# AmbientLight-2.net
KiCad netlist of a schematic drawn in EAGLE
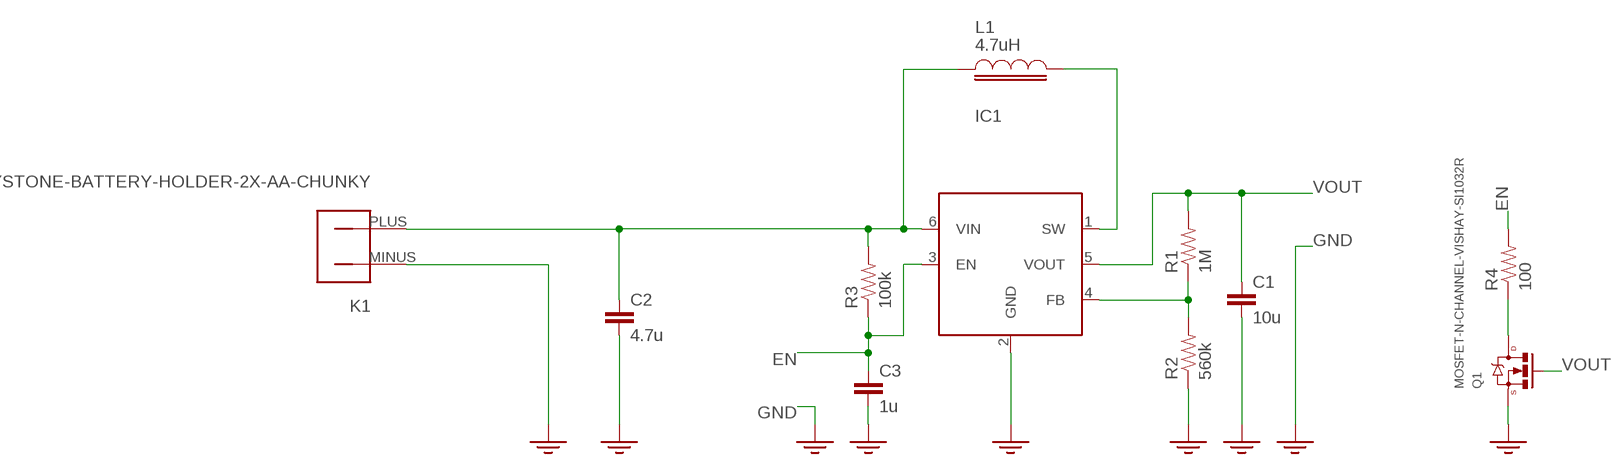
[diagram p0: schematic, sheet 1]

(export (version "E")
  (design (tool "Eeschema 10.0.6"))
  (components
    (comp (ref "C1")
      (value "10u")
      (footprint "eagle-import:0805-WIDE")
      (libsource (lib "eagle-import") (part "CAP-0805-WIDE"))
    )
    (comp (ref "C2")
      (value "4.7u")
      (footprint "eagle-import:0603-MIN")
      (libsource (lib "eagle-import") (part "CAP-0603-MIN"))
    )
    (comp (ref "C3")
      (value "1u")
      (footprint "eagle-import:0603-MIN")
      (libsource (lib "eagle-import") (part "CAP-0603-MIN"))
    )
    (comp (ref "IC1")
      (value "SWITCHING-REGULATOR-VARIABLE-BOOST-MCP1640")
      (footprint "eagle-import:SOT23-6")
      (libsource (lib "eagle-import") (part "SWITCHING-REGULATOR-VARIABLE-BOOST-MCP1640"))
    )
    (comp (ref "K1")
      (value "KEYSTONE-BATTERY-HOLDER-2X-AA-CHUNKY")
      (footprint "eagle-import:KEYSTONE-BATTERY-HOLDER-2X-AA-CHUNKY")
      (libsource (lib "eagle-import") (part "KEYSTONE-BATTERY-HOLDER-2X-AA-CHUNKY"))
    )
    (comp (ref "L1")
      (value "4.7uH")
      (footprint "eagle-import:1210-INDUCTOR-MIN")
      (libsource (lib "eagle-import") (part "INDUCTOR-1210-MIN"))
    )
    (comp (ref "Q1")
      (value "MOSFET-N-CHANNEL-VISHAY-SI1032R")
      (footprint "eagle-import:SC-75A")
      (libsource (lib "eagle-import") (part "MOSFET-N-CHANNEL-VISHAY-SI1032R"))
    )
    (comp (ref "R1")
      (value "1M")
      (footprint "eagle-import:0603-MIN")
      (libsource (lib "eagle-import") (part "RESISTOR-0603-MIN"))
    )
    (comp (ref "R2")
      (value "560k")
      (footprint "eagle-import:0603-MIN")
      (libsource (lib "eagle-import") (part "RESISTOR-0603-MIN"))
    )
    (comp (ref "R3")
      (value "100k")
      (footprint "eagle-import:0603-MIN")
      (libsource (lib "eagle-import") (part "RESISTOR-0603-MIN"))
    )
    (comp (ref "R4")
      (value "100")
      (footprint "eagle-import:0603-MIN")
      (libsource (lib "eagle-import") (part "RESISTOR-0603-MIN"))
    )
  )
  (nets
    (net (code "1") (name "/EN") (class "Default")
      (node (ref "C3") (pin "2") (pinfunction "2_2") (pintype "bidirectional"))
      (node (ref "IC1") (pin "3") (pinfunction "EN_3") (pintype "bidirectional"))
      (node (ref "R3") (pin "1") (pinfunction "1_1") (pintype "passive"))
      (node (ref "R4") (pin "2") (pinfunction "2_2") (pintype "passive"))
    )
    (net (code "2") (name "/VOUT") (class "Default")
      (node (ref "C1") (pin "2") (pinfunction "2_2") (pintype "bidirectional"))
      (node (ref "IC1") (pin "5") (pinfunction "VOUT_5") (pintype "bidirectional"))
      (node (ref "Q1") (pin "1") (pinfunction "GATE_1") (pintype "bidirectional"))
      (node (ref "R1") (pin "2") (pinfunction "2_2") (pintype "passive"))
    )
    (net (code "3") (name "GND") (class "Default")
      (node (ref "C1") (pin "1") (pinfunction "1_1") (pintype "bidirectional"))
      (node (ref "C2") (pin "1") (pinfunction "1_1") (pintype "bidirectional"))
      (node (ref "C3") (pin "1") (pinfunction "1_1") (pintype "bidirectional"))
      (node (ref "IC1") (pin "2") (pinfunction "GND_2") (pintype "bidirectional"))
      (node (ref "K1") (pin "MINUS") (pinfunction "PLUS_MINUS") (pintype "power_in"))
      (node (ref "Q1") (pin "2") (pinfunction "SOURCE_2") (pintype "bidirectional"))
      (node (ref "R2") (pin "1") (pinfunction "1_1") (pintype "passive"))
    )
    (net (code "4") (name "Net-(IC1-FB)") (class "Default")
      (node (ref "IC1") (pin "4") (pinfunction "FB_4") (pintype "bidirectional"))
      (node (ref "R1") (pin "1") (pinfunction "1_1") (pintype "passive"))
      (node (ref "R2") (pin "2") (pinfunction "2_2") (pintype "passive"))
    )
    (net (code "5") (name "Net-(IC1-SW)") (class "Default")
      (node (ref "IC1") (pin "1") (pinfunction "SW_1") (pintype "bidirectional"))
      (node (ref "L1") (pin "2") (pinfunction "2_2") (pintype "bidirectional"))
    )
    (net (code "6") (name "Net-(IC1-VIN)") (class "Default")
      (node (ref "C2") (pin "2") (pinfunction "2_2") (pintype "bidirectional"))
      (node (ref "IC1") (pin "6") (pinfunction "VIN_6") (pintype "bidirectional"))
      (node (ref "K1") (pin "PLUS") (pinfunction "MINUS_PLUS") (pintype "power_in"))
      (node (ref "L1") (pin "1") (pinfunction "1_1") (pintype "bidirectional"))
      (node (ref "R3") (pin "2") (pinfunction "2_2") (pintype "passive"))
    )
    (net (code "7") (name "Net-(Q1-DRAIN)") (class "Default")
      (node (ref "Q1") (pin "3") (pinfunction "DRAIN_3") (pintype "bidirectional"))
      (node (ref "R4") (pin "1") (pinfunction "1_1") (pintype "passive"))
    )
  )
)
